# HSADDAPower.net
KiCad netlist of a schematic drawn in Altium Designer
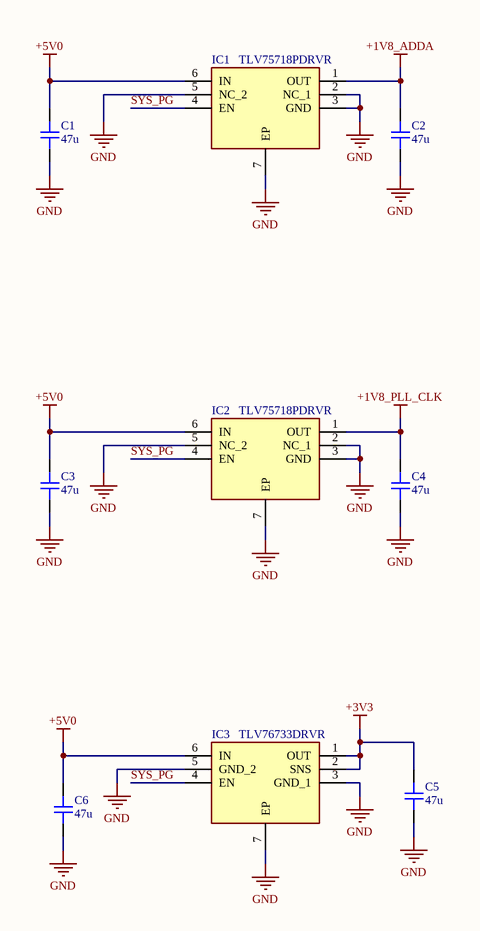
[diagram p0: HSADDAPower.SchDoc]

(export (version "E")
  (design (tool "Eeschema 10.0.6"))
  (components
    (comp (ref "C1")
      (value "47u")
      (footprint "CAP_0805")
      (description "Capacitor SMD 0805")
      (libsource (lib "Schematic-Lib-PhilsLab") (part "CAP_0805"))
    )
    (comp (ref "C2")
      (value "47u")
      (footprint "CAP_0805")
      (description "Capacitor SMD 0805")
      (libsource (lib "Schematic-Lib-PhilsLab") (part "CAP_0805"))
    )
    (comp (ref "C3")
      (value "47u")
      (footprint "CAP_0805")
      (description "Capacitor SMD 0805")
      (libsource (lib "Schematic-Lib-PhilsLab") (part "CAP_0805"))
    )
    (comp (ref "C4")
      (value "47u")
      (footprint "CAP_0805")
      (description "Capacitor SMD 0805")
      (libsource (lib "Schematic-Lib-PhilsLab") (part "CAP_0805"))
    )
    (comp (ref "C5")
      (value "47u")
      (footprint "CAP_0805")
      (description "Capacitor SMD 0805")
      (libsource (lib "Schematic-Lib-PhilsLab") (part "CAP_0805"))
    )
    (comp (ref "C6")
      (value "47u")
      (footprint "CAP_0805")
      (description "Capacitor SMD 0805")
      (libsource (lib "Schematic-Lib-PhilsLab") (part "CAP_0805"))
    )
    (comp (ref "IC1")
      (value "TLV75718PDRVR")
      (footprint "JetsonTx2_PCBLib:SON65P200X200X80-7N")
      (description "Integrated Circuit")
      (fields (field (name "MOUSER PART NUMBER") "595-TLV75718PDRVR"))
      (libsource (lib "JetsonTx2_SCHLib") (part "TLV75718PDRVR"))
    )
    (comp (ref "IC2")
      (value "TLV75718PDRVR")
      (footprint "JetsonTx2_PCBLib:SON65P200X200X80-7N")
      (description "Integrated Circuit")
      (fields (field (name "MOUSER PART NUMBER") "595-TLV75718PDRVR"))
      (libsource (lib "JetsonTx2_SCHLib") (part "TLV75718PDRVR"))
    )
    (comp (ref "IC3")
      (value "TLV76733DRVR")
      (footprint "JetsonTx2_PCBLib:SON65P200X200X80-7N")
      (description "Integrated Circuit")
      (fields (field (name "MOUSER PART NUMBER") "595-TLV76733DRVR"))
      (libsource (lib "JetsonTx2_SCHLib") (part "TLV76733DRVR"))
    )
  )
  (nets
    (net (code "1") (name "+1V8_ADDA") (class "Default")
      (node (ref "C2") (pin "2") (pinfunction "2_2") (pintype "passive"))
      (node (ref "IC1") (pin "1") (pinfunction "OUT_1") (pintype "passive"))
    )
    (net (code "2") (name "+1V8_PLL_CLK") (class "Default")
      (node (ref "C4") (pin "2") (pinfunction "2_2") (pintype "passive"))
      (node (ref "IC2") (pin "1") (pinfunction "OUT_1") (pintype "passive"))
    )
    (net (code "3") (name "+3V3") (class "Default")
      (node (ref "C5") (pin "2") (pinfunction "2_2") (pintype "passive"))
      (node (ref "IC3") (pin "1") (pinfunction "OUT_1") (pintype "passive"))
      (node (ref "IC3") (pin "2") (pinfunction "SNS_2") (pintype "passive"))
    )
    (net (code "4") (name "+5V0") (class "Default")
      (node (ref "C1") (pin "2") (pinfunction "2_2") (pintype "passive"))
      (node (ref "C3") (pin "2") (pinfunction "2_2") (pintype "passive"))
      (node (ref "C6") (pin "2") (pinfunction "2_2") (pintype "passive"))
      (node (ref "IC1") (pin "6") (pinfunction "IN_6") (pintype "passive"))
      (node (ref "IC2") (pin "6") (pinfunction "IN_6") (pintype "passive"))
      (node (ref "IC3") (pin "6") (pinfunction "IN_6") (pintype "passive"))
    )
    (net (code "5") (name "/SYS_PG") (class "Default")
      (node (ref "IC1") (pin "4") (pinfunction "EN_4") (pintype "passive"))
      (node (ref "IC2") (pin "4") (pinfunction "EN_4") (pintype "passive"))
      (node (ref "IC3") (pin "4") (pinfunction "EN_4") (pintype "passive"))
    )
    (net (code "6") (name "GND") (class "Default")
      (node (ref "C1") (pin "1") (pinfunction "1_1") (pintype "passive"))
      (node (ref "C2") (pin "1") (pinfunction "1_1") (pintype "passive"))
      (node (ref "C3") (pin "1") (pinfunction "1_1") (pintype "passive"))
      (node (ref "C4") (pin "1") (pinfunction "1_1") (pintype "passive"))
      (node (ref "C5") (pin "1") (pinfunction "1_1") (pintype "passive"))
      (node (ref "C6") (pin "1") (pinfunction "1_1") (pintype "passive"))
      (node (ref "IC1") (pin "2") (pinfunction "NC_1_2") (pintype "passive"))
      (node (ref "IC1") (pin "3") (pinfunction "GND_3") (pintype "passive"))
      (node (ref "IC1") (pin "5") (pinfunction "NC_2_5") (pintype "passive"))
      (node (ref "IC1") (pin "7") (pinfunction "EP_7") (pintype "passive"))
      (node (ref "IC2") (pin "2") (pinfunction "NC_1_2") (pintype "passive"))
      (node (ref "IC2") (pin "3") (pinfunction "GND_3") (pintype "passive"))
      (node (ref "IC2") (pin "5") (pinfunction "NC_2_5") (pintype "passive"))
      (node (ref "IC2") (pin "7") (pinfunction "EP_7") (pintype "passive"))
      (node (ref "IC3") (pin "3") (pinfunction "GND_1_3") (pintype "passive"))
      (node (ref "IC3") (pin "5") (pinfunction "GND_2_5") (pintype "passive"))
      (node (ref "IC3") (pin "7") (pinfunction "EP_7") (pintype "passive"))
    )
  )
)
